# Faced.net
KiCad netlist of a schematic drawn in EAGLE
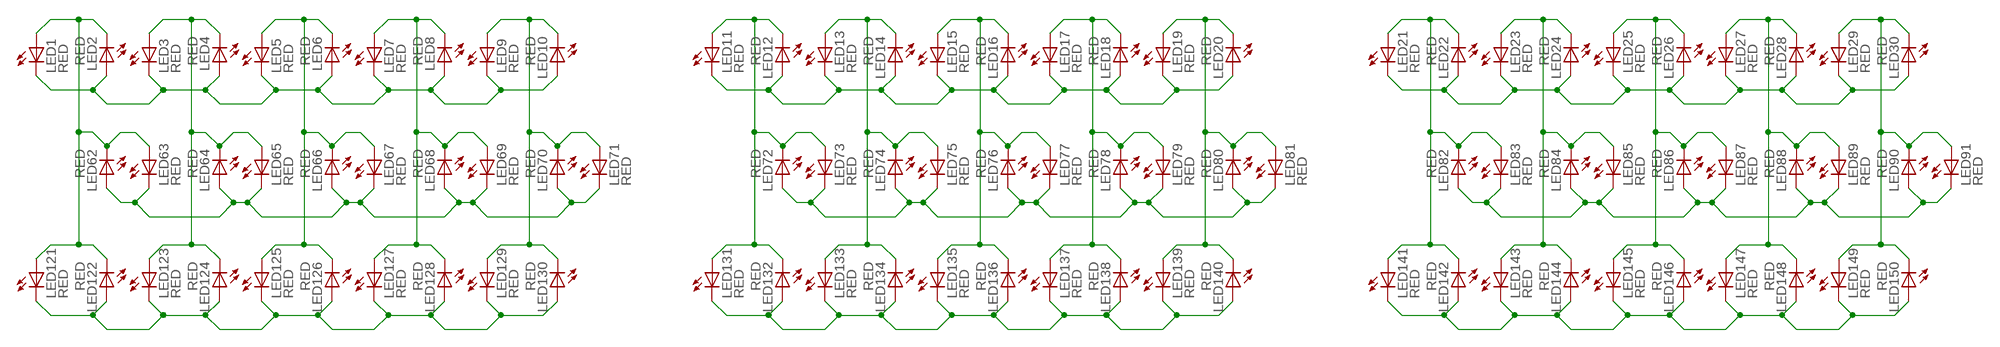
[diagram p0: schematic, sheet 1, part 1 of 2]
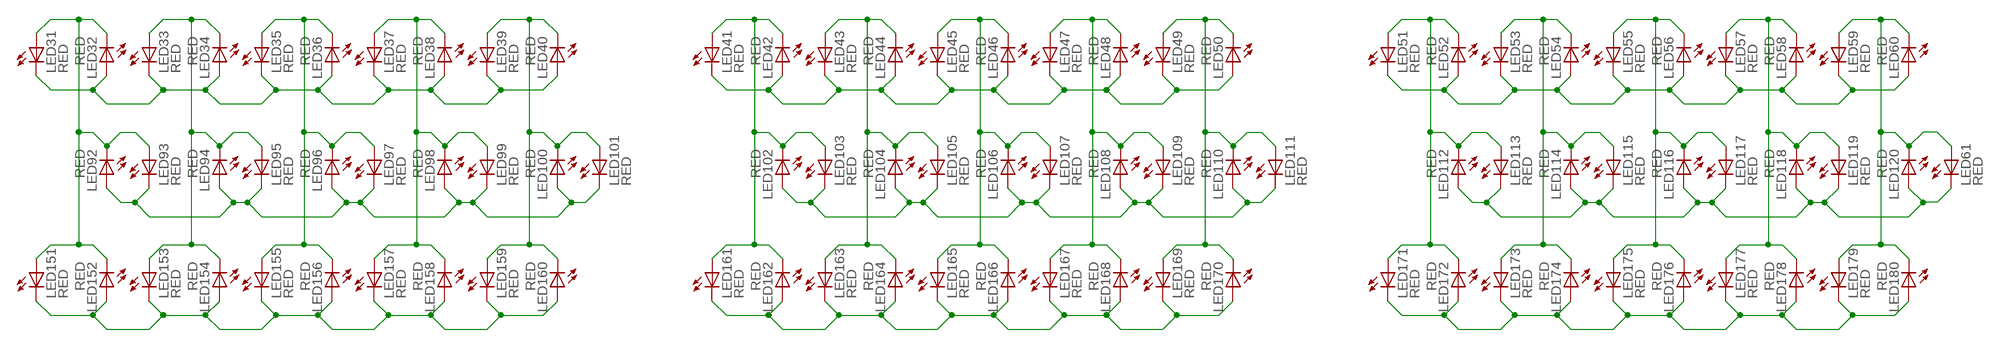
[diagram p1: schematic, sheet 1, part 2 of 2]

(export (version "E")
  (design (tool "Eeschema 10.0.6"))
  (components
    (comp (ref "LED1")
      (value "RED")
      (footprint "eagle-import:LED-0603")
      (libsource (lib "eagle-import") (part "LED0603"))
    )
    (comp (ref "LED2")
      (value "RED")
      (footprint "eagle-import:LED-0603")
      (libsource (lib "eagle-import") (part "LED0603"))
    )
    (comp (ref "LED3")
      (value "RED")
      (footprint "eagle-import:LED-0603")
      (libsource (lib "eagle-import") (part "LED0603"))
    )
    (comp (ref "LED4")
      (value "RED")
      (footprint "eagle-import:LED-0603")
      (libsource (lib "eagle-import") (part "LED0603"))
    )
    (comp (ref "LED5")
      (value "RED")
      (footprint "eagle-import:LED-0603")
      (libsource (lib "eagle-import") (part "LED0603"))
    )
    (comp (ref "LED6")
      (value "RED")
      (footprint "eagle-import:LED-0603")
      (libsource (lib "eagle-import") (part "LED0603"))
    )
    (comp (ref "LED7")
      (value "RED")
      (footprint "eagle-import:LED-0603")
      (libsource (lib "eagle-import") (part "LED0603"))
    )
    (comp (ref "LED8")
      (value "RED")
      (footprint "eagle-import:LED-0603")
      (libsource (lib "eagle-import") (part "LED0603"))
    )
    (comp (ref "LED9")
      (value "RED")
      (footprint "eagle-import:LED-0603")
      (libsource (lib "eagle-import") (part "LED0603"))
    )
    (comp (ref "LED10")
      (value "RED")
      (footprint "eagle-import:LED-0603")
      (libsource (lib "eagle-import") (part "LED0603"))
    )
    (comp (ref "LED11")
      (value "RED")
      (footprint "eagle-import:LED-0603")
      (libsource (lib "eagle-import") (part "LED0603"))
    )
    (comp (ref "LED12")
      (value "RED")
      (footprint "eagle-import:LED-0603")
      (libsource (lib "eagle-import") (part "LED0603"))
    )
    (comp (ref "LED13")
      (value "RED")
      (footprint "eagle-import:LED-0603")
      (libsource (lib "eagle-import") (part "LED0603"))
    )
    (comp (ref "LED14")
      (value "RED")
      (footprint "eagle-import:LED-0603")
      (libsource (lib "eagle-import") (part "LED0603"))
    )
    (comp (ref "LED15")
      (value "RED")
      (footprint "eagle-import:LED-0603")
      (libsource (lib "eagle-import") (part "LED0603"))
    )
    (comp (ref "LED16")
      (value "RED")
      (footprint "eagle-import:LED-0603")
      (libsource (lib "eagle-import") (part "LED0603"))
    )
    (comp (ref "LED17")
      (value "RED")
      (footprint "eagle-import:LED-0603")
      (libsource (lib "eagle-import") (part "LED0603"))
    )
    (comp (ref "LED18")
      (value "RED")
      (footprint "eagle-import:LED-0603")
      (libsource (lib "eagle-import") (part "LED0603"))
    )
    (comp (ref "LED19")
      (value "RED")
      (footprint "eagle-import:LED-0603")
      (libsource (lib "eagle-import") (part "LED0603"))
    )
    (comp (ref "LED20")
      (value "RED")
      (footprint "eagle-import:LED-0603")
      (libsource (lib "eagle-import") (part "LED0603"))
    )
    (comp (ref "LED21")
      (value "RED")
      (footprint "eagle-import:LED-0603")
      (libsource (lib "eagle-import") (part "LED0603"))
    )
    (comp (ref "LED22")
      (value "RED")
      (footprint "eagle-import:LED-0603")
      (libsource (lib "eagle-import") (part "LED0603"))
    )
    (comp (ref "LED23")
      (value "RED")
      (footprint "eagle-import:LED-0603")
      (libsource (lib "eagle-import") (part "LED0603"))
    )
    (comp (ref "LED24")
      (value "RED")
      (footprint "eagle-import:LED-0603")
      (libsource (lib "eagle-import") (part "LED0603"))
    )
    (comp (ref "LED25")
      (value "RED")
      (footprint "eagle-import:LED-0603")
      (libsource (lib "eagle-import") (part "LED0603"))
    )
    (comp (ref "LED26")
      (value "RED")
      (footprint "eagle-import:LED-0603")
      (libsource (lib "eagle-import") (part "LED0603"))
    )
    (comp (ref "LED27")
      (value "RED")
      (footprint "eagle-import:LED-0603")
      (libsource (lib "eagle-import") (part "LED0603"))
    )
    (comp (ref "LED28")
      (value "RED")
      (footprint "eagle-import:LED-0603")
      (libsource (lib "eagle-import") (part "LED0603"))
    )
    (comp (ref "LED29")
      (value "RED")
      (footprint "eagle-import:LED-0603")
      (libsource (lib "eagle-import") (part "LED0603"))
    )
    (comp (ref "LED30")
      (value "RED")
      (footprint "eagle-import:LED-0603")
      (libsource (lib "eagle-import") (part "LED0603"))
    )
    (comp (ref "LED31")
      (value "RED")
      (footprint "eagle-import:LED-0603")
      (libsource (lib "eagle-import") (part "LED0603"))
    )
    (comp (ref "LED32")
      (value "RED")
      (footprint "eagle-import:LED-0603")
      (libsource (lib "eagle-import") (part "LED0603"))
    )
    (comp (ref "LED33")
      (value "RED")
      (footprint "eagle-import:LED-0603")
      (libsource (lib "eagle-import") (part "LED0603"))
    )
    (comp (ref "LED34")
      (value "RED")
      (footprint "eagle-import:LED-0603")
      (libsource (lib "eagle-import") (part "LED0603"))
    )
    (comp (ref "LED35")
      (value "RED")
      (footprint "eagle-import:LED-0603")
      (libsource (lib "eagle-import") (part "LED0603"))
    )
    (comp (ref "LED36")
      (value "RED")
      (footprint "eagle-import:LED-0603")
      (libsource (lib "eagle-import") (part "LED0603"))
    )
    (comp (ref "LED37")
      (value "RED")
      (footprint "eagle-import:LED-0603")
      (libsource (lib "eagle-import") (part "LED0603"))
    )
    (comp (ref "LED38")
      (value "RED")
      (footprint "eagle-import:LED-0603")
      (libsource (lib "eagle-import") (part "LED0603"))
    )
    (comp (ref "LED39")
      (value "RED")
      (footprint "eagle-import:LED-0603")
      (libsource (lib "eagle-import") (part "LED0603"))
    )
    (comp (ref "LED40")
      (value "RED")
      (footprint "eagle-import:LED-0603")
      (libsource (lib "eagle-import") (part "LED0603"))
    )
    (comp (ref "LED41")
      (value "RED")
      (footprint "eagle-import:LED-0603")
      (libsource (lib "eagle-import") (part "LED0603"))
    )
    (comp (ref "LED42")
      (value "RED")
      (footprint "eagle-import:LED-0603")
      (libsource (lib "eagle-import") (part "LED0603"))
    )
    (comp (ref "LED43")
      (value "RED")
      (footprint "eagle-import:LED-0603")
      (libsource (lib "eagle-import") (part "LED0603"))
    )
    (comp (ref "LED44")
      (value "RED")
      (footprint "eagle-import:LED-0603")
      (libsource (lib "eagle-import") (part "LED0603"))
    )
    (comp (ref "LED45")
      (value "RED")
      (footprint "eagle-import:LED-0603")
      (libsource (lib "eagle-import") (part "LED0603"))
    )
    (comp (ref "LED46")
      (value "RED")
      (footprint "eagle-import:LED-0603")
      (libsource (lib "eagle-import") (part "LED0603"))
    )
    (comp (ref "LED47")
      (value "RED")
      (footprint "eagle-import:LED-0603")
      (libsource (lib "eagle-import") (part "LED0603"))
    )
    (comp (ref "LED48")
      (value "RED")
      (footprint "eagle-import:LED-0603")
      (libsource (lib "eagle-import") (part "LED0603"))
    )
    (comp (ref "LED49")
      (value "RED")
      (footprint "eagle-import:LED-0603")
      (libsource (lib "eagle-import") (part "LED0603"))
    )
    (comp (ref "LED50")
      (value "RED")
      (footprint "eagle-import:LED-0603")
      (libsource (lib "eagle-import") (part "LED0603"))
    )
    (comp (ref "LED51")
      (value "RED")
      (footprint "eagle-import:LED-0603")
      (libsource (lib "eagle-import") (part "LED0603"))
    )
    (comp (ref "LED52")
      (value "RED")
      (footprint "eagle-import:LED-0603")
      (libsource (lib "eagle-import") (part "LED0603"))
    )
    (comp (ref "LED53")
      (value "RED")
      (footprint "eagle-import:LED-0603")
      (libsource (lib "eagle-import") (part "LED0603"))
    )
    (comp (ref "LED54")
      (value "RED")
      (footprint "eagle-import:LED-0603")
      (libsource (lib "eagle-import") (part "LED0603"))
    )
    (comp (ref "LED55")
      (value "RED")
      (footprint "eagle-import:LED-0603")
      (libsource (lib "eagle-import") (part "LED0603"))
    )
    (comp (ref "LED56")
      (value "RED")
      (footprint "eagle-import:LED-0603")
      (libsource (lib "eagle-import") (part "LED0603"))
    )
    (comp (ref "LED57")
      (value "RED")
      (footprint "eagle-import:LED-0603")
      (libsource (lib "eagle-import") (part "LED0603"))
    )
    (comp (ref "LED58")
      (value "RED")
      (footprint "eagle-import:LED-0603")
      (libsource (lib "eagle-import") (part "LED0603"))
    )
    (comp (ref "LED59")
      (value "RED")
      (footprint "eagle-import:LED-0603")
      (libsource (lib "eagle-import") (part "LED0603"))
    )
    (comp (ref "LED60")
      (value "RED")
      (footprint "eagle-import:LED-0603")
      (libsource (lib "eagle-import") (part "LED0603"))
    )
    (comp (ref "LED61")
      (value "RED")
      (footprint "eagle-import:LED-0603")
      (libsource (lib "eagle-import") (part "LED0603"))
    )
    (comp (ref "LED62")
      (value "RED")
      (footprint "eagle-import:LED-0603")
      (libsource (lib "eagle-import") (part "LED0603"))
    )
    (comp (ref "LED63")
      (value "RED")
      (footprint "eagle-import:LED-0603")
      (libsource (lib "eagle-import") (part "LED0603"))
    )
    (comp (ref "LED64")
      (value "RED")
      (footprint "eagle-import:LED-0603")
      (libsource (lib "eagle-import") (part "LED0603"))
    )
    (comp (ref "LED65")
      (value "RED")
      (footprint "eagle-import:LED-0603")
      (libsource (lib "eagle-import") (part "LED0603"))
    )
    (comp (ref "LED66")
      (value "RED")
      (footprint "eagle-import:LED-0603")
      (libsource (lib "eagle-import") (part "LED0603"))
    )
    (comp (ref "LED67")
      (value "RED")
      (footprint "eagle-import:LED-0603")
      (libsource (lib "eagle-import") (part "LED0603"))
    )
    (comp (ref "LED68")
      (value "RED")
      (footprint "eagle-import:LED-0603")
      (libsource (lib "eagle-import") (part "LED0603"))
    )
    (comp (ref "LED69")
      (value "RED")
      (footprint "eagle-import:LED-0603")
      (libsource (lib "eagle-import") (part "LED0603"))
    )
    (comp (ref "LED70")
      (value "RED")
      (footprint "eagle-import:LED-0603")
      (libsource (lib "eagle-import") (part "LED0603"))
    )
    (comp (ref "LED71")
      (value "RED")
      (footprint "eagle-import:LED-0603")
      (libsource (lib "eagle-import") (part "LED0603"))
    )
    (comp (ref "LED72")
      (value "RED")
      (footprint "eagle-import:LED-0603")
      (libsource (lib "eagle-import") (part "LED0603"))
    )
    (comp (ref "LED73")
      (value "RED")
      (footprint "eagle-import:LED-0603")
      (libsource (lib "eagle-import") (part "LED0603"))
    )
    (comp (ref "LED74")
      (value "RED")
      (footprint "eagle-import:LED-0603")
      (libsource (lib "eagle-import") (part "LED0603"))
    )
    (comp (ref "LED75")
      (value "RED")
      (footprint "eagle-import:LED-0603")
      (libsource (lib "eagle-import") (part "LED0603"))
    )
    (comp (ref "LED76")
      (value "RED")
      (footprint "eagle-import:LED-0603")
      (libsource (lib "eagle-import") (part "LED0603"))
    )
    (comp (ref "LED77")
      (value "RED")
      (footprint "eagle-import:LED-0603")
      (libsource (lib "eagle-import") (part "LED0603"))
    )
    (comp (ref "LED78")
      (value "RED")
      (footprint "eagle-import:LED-0603")
      (libsource (lib "eagle-import") (part "LED0603"))
    )
    (comp (ref "LED79")
      (value "RED")
      (footprint "eagle-import:LED-0603")
      (libsource (lib "eagle-import") (part "LED0603"))
    )
    (comp (ref "LED80")
      (value "RED")
      (footprint "eagle-import:LED-0603")
      (libsource (lib "eagle-import") (part "LED0603"))
    )
    (comp (ref "LED81")
      (value "RED")
      (footprint "eagle-import:LED-0603")
      (libsource (lib "eagle-import") (part "LED0603"))
    )
    (comp (ref "LED82")
      (value "RED")
      (footprint "eagle-import:LED-0603")
      (libsource (lib "eagle-import") (part "LED0603"))
    )
    (comp (ref "LED83")
      (value "RED")
      (footprint "eagle-import:LED-0603")
      (libsource (lib "eagle-import") (part "LED0603"))
    )
    (comp (ref "LED84")
      (value "RED")
      (footprint "eagle-import:LED-0603")
      (libsource (lib "eagle-import") (part "LED0603"))
    )
    (comp (ref "LED85")
      (value "RED")
      (footprint "eagle-import:LED-0603")
      (libsource (lib "eagle-import") (part "LED0603"))
    )
    (comp (ref "LED86")
      (value "RED")
      (footprint "eagle-import:LED-0603")
      (libsource (lib "eagle-import") (part "LED0603"))
    )
    (comp (ref "LED87")
      (value "RED")
      (footprint "eagle-import:LED-0603")
      (libsource (lib "eagle-import") (part "LED0603"))
    )
    (comp (ref "LED88")
      (value "RED")
      (footprint "eagle-import:LED-0603")
      (libsource (lib "eagle-import") (part "LED0603"))
    )
    (comp (ref "LED89")
      (value "RED")
      (footprint "eagle-import:LED-0603")
      (libsource (lib "eagle-import") (part "LED0603"))
    )
    (comp (ref "LED90")
      (value "RED")
      (footprint "eagle-import:LED-0603")
      (libsource (lib "eagle-import") (part "LED0603"))
    )
    (comp (ref "LED91")
      (value "RED")
      (footprint "eagle-import:LED-0603")
      (libsource (lib "eagle-import") (part "LED0603"))
    )
    (comp (ref "LED92")
      (value "RED")
      (footprint "eagle-import:LED-0603")
      (libsource (lib "eagle-import") (part "LED0603"))
    )
    (comp (ref "LED93")
      (value "RED")
      (footprint "eagle-import:LED-0603")
      (libsource (lib "eagle-import") (part "LED0603"))
    )
    (comp (ref "LED94")
      (value "RED")
      (footprint "eagle-import:LED-0603")
      (libsource (lib "eagle-import") (part "LED0603"))
    )
    (comp (ref "LED95")
      (value "RED")
      (footprint "eagle-import:LED-0603")
      (libsource (lib "eagle-import") (part "LED0603"))
    )
    (comp (ref "LED96")
      (value "RED")
      (footprint "eagle-import:LED-0603")
      (libsource (lib "eagle-import") (part "LED0603"))
    )
    (comp (ref "LED97")
      (value "RED")
      (footprint "eagle-import:LED-0603")
      (libsource (lib "eagle-import") (part "LED0603"))
    )
    (comp (ref "LED98")
      (value "RED")
      (footprint "eagle-import:LED-0603")
      (libsource (lib "eagle-import") (part "LED0603"))
    )
    (comp (ref "LED99")
      (value "RED")
      (footprint "eagle-import:LED-0603")
      (libsource (lib "eagle-import") (part "LED0603"))
    )
    (comp (ref "LED100")
      (value "RED")
      (footprint "eagle-import:LED-0603")
      (libsource (lib "eagle-import") (part "LED0603"))
    )
    (comp (ref "LED101")
      (value "RED")
      (footprint "eagle-import:LED-0603")
      (libsource (lib "eagle-import") (part "LED0603"))
    )
    (comp (ref "LED102")
      (value "RED")
      (footprint "eagle-import:LED-0603")
      (libsource (lib "eagle-import") (part "LED0603"))
    )
    (comp (ref "LED103")
      (value "RED")
      (footprint "eagle-import:LED-0603")
      (libsource (lib "eagle-import") (part "LED0603"))
    )
    (comp (ref "LED104")
      (value "RED")
      (footprint "eagle-import:LED-0603")
      (libsource (lib "eagle-import") (part "LED0603"))
    )
    (comp (ref "LED105")
      (value "RED")
      (footprint "eagle-import:LED-0603")
      (libsource (lib "eagle-import") (part "LED0603"))
    )
    (comp (ref "LED106")
      (value "RED")
      (footprint "eagle-import:LED-0603")
      (libsource (lib "eagle-import") (part "LED0603"))
    )
    (comp (ref "LED107")
      (value "RED")
      (footprint "eagle-import:LED-0603")
      (libsource (lib "eagle-import") (part "LED0603"))
    )
    (comp (ref "LED108")
      (value "RED")
      (footprint "eagle-import:LED-0603")
      (libsource (lib "eagle-import") (part "LED0603"))
    )
    (comp (ref "LED109")
      (value "RED")
      (footprint "eagle-import:LED-0603")
      (libsource (lib "eagle-import") (part "LED0603"))
    )
    (comp (ref "LED110")
      (value "RED")
      (footprint "eagle-import:LED-0603")
      (libsource (lib "eagle-import") (part "LED0603"))
    )
    (comp (ref "LED111")
      (value "RED")
      (footprint "eagle-import:LED-0603")
      (libsource (lib "eagle-import") (part "LED0603"))
    )
    (comp (ref "LED112")
      (value "RED")
      (footprint "eagle-import:LED-0603")
      (libsource (lib "eagle-import") (part "LED0603"))
    )
    (comp (ref "LED113")
      (value "RED")
      (footprint "eagle-import:LED-0603")
      (libsource (lib "eagle-import") (part "LED0603"))
    )
    (comp (ref "LED114")
      (value "RED")
      (footprint "eagle-import:LED-0603")
      (libsource (lib "eagle-import") (part "LED0603"))
    )
    (comp (ref "LED115")
      (value "RED")
      (footprint "eagle-import:LED-0603")
      (libsource (lib "eagle-import") (part "LED0603"))
    )
    (comp (ref "LED116")
      (value "RED")
      (footprint "eagle-import:LED-0603")
      (libsource (lib "eagle-import") (part "LED0603"))
    )
    (comp (ref "LED117")
      (value "RED")
      (footprint "eagle-import:LED-0603")
      (libsource (lib "eagle-import") (part "LED0603"))
    )
    (comp (ref "LED118")
      (value "RED")
      (footprint "eagle-import:LED-0603")
      (libsource (lib "eagle-import") (part "LED0603"))
    )
    (comp (ref "LED119")
      (value "RED")
      (footprint "eagle-import:LED-0603")
      (libsource (lib "eagle-import") (part "LED0603"))
    )
    (comp (ref "LED120")
      (value "RED")
      (footprint "eagle-import:LED-0603")
      (libsource (lib "eagle-import") (part "LED0603"))
    )
    (comp (ref "LED121")
      (value "RED")
      (footprint "eagle-import:LED-0603")
      (libsource (lib "eagle-import") (part "LED0603"))
    )
    (comp (ref "LED122")
      (value "RED")
      (footprint "eagle-import:LED-0603")
      (libsource (lib "eagle-import") (part "LED0603"))
    )
    (comp (ref "LED123")
      (value "RED")
      (footprint "eagle-import:LED-0603")
      (libsource (lib "eagle-import") (part "LED0603"))
    )
    (comp (ref "LED124")
      (value "RED")
      (footprint "eagle-import:LED-0603")
      (libsource (lib "eagle-import") (part "LED0603"))
    )
    (comp (ref "LED125")
      (value "RED")
      (footprint "eagle-import:LED-0603")
      (libsource (lib "eagle-import") (part "LED0603"))
    )
    (comp (ref "LED126")
      (value "RED")
      (footprint "eagle-import:LED-0603")
      (libsource (lib "eagle-import") (part "LED0603"))
    )
    (comp (ref "LED127")
      (value "RED")
      (footprint "eagle-import:LED-0603")
      (libsource (lib "eagle-import") (part "LED0603"))
    )
    (comp (ref "LED128")
      (value "RED")
      (footprint "eagle-import:LED-0603")
      (libsource (lib "eagle-import") (part "LED0603"))
    )
    (comp (ref "LED129")
      (value "RED")
      (footprint "eagle-import:LED-0603")
      (libsource (lib "eagle-import") (part "LED0603"))
    )
    (comp (ref "LED130")
      (value "RED")
      (footprint "eagle-import:LED-0603")
      (libsource (lib "eagle-import") (part "LED0603"))
    )
    (comp (ref "LED131")
      (value "RED")
      (footprint "eagle-import:LED-0603")
      (libsource (lib "eagle-import") (part "LED0603"))
    )
    (comp (ref "LED132")
      (value "RED")
      (footprint "eagle-import:LED-0603")
      (libsource (lib "eagle-import") (part "LED0603"))
    )
    (comp (ref "LED133")
      (value "RED")
      (footprint "eagle-import:LED-0603")
      (libsource (lib "eagle-import") (part "LED0603"))
    )
    (comp (ref "LED134")
      (value "RED")
      (footprint "eagle-import:LED-0603")
      (libsource (lib "eagle-import") (part "LED0603"))
    )
    (comp (ref "LED135")
      (value "RED")
      (footprint "eagle-import:LED-0603")
      (libsource (lib "eagle-import") (part "LED0603"))
    )
    (comp (ref "LED136")
      (value "RED")
      (footprint "eagle-import:LED-0603")
      (libsource (lib "eagle-import") (part "LED0603"))
    )
    (comp (ref "LED137")
      (value "RED")
      (footprint "eagle-import:LED-0603")
      (libsource (lib "eagle-import") (part "LED0603"))
    )
    (comp (ref "LED138")
      (value "RED")
      (footprint "eagle-import:LED-0603")
      (libsource (lib "eagle-import") (part "LED0603"))
    )
    (comp (ref "LED139")
      (value "RED")
      (footprint "eagle-import:LED-0603")
      (libsource (lib "eagle-import") (part "LED0603"))
    )
    (comp (ref "LED140")
      (value "RED")
      (footprint "eagle-import:LED-0603")
      (libsource (lib "eagle-import") (part "LED0603"))
    )
    (comp (ref "LED141")
      (value "RED")
      (footprint "eagle-import:LED-0603")
      (libsource (lib "eagle-import") (part "LED0603"))
    )
    (comp (ref "LED142")
      (value "RED")
      (footprint "eagle-import:LED-0603")
      (libsource (lib "eagle-import") (part "LED0603"))
    )
    (comp (ref "LED143")
      (value "RED")
      (footprint "eagle-import:LED-0603")
      (libsource (lib "eagle-import") (part "LED0603"))
    )
    (comp (ref "LED144")
      (value "RED")
      (footprint "eagle-import:LED-0603")
      (libsource (lib "eagle-import") (part "LED0603"))
    )
    (comp (ref "LED145")
      (value "RED")
      (footprint "eagle-import:LED-0603")
      (libsource (lib "eagle-import") (part "LED0603"))
    )
    (comp (ref "LED146")
      (value "RED")
      (footprint "eagle-import:LED-0603")
      (libsource (lib "eagle-import") (part "LED0603"))
    )
    (comp (ref "LED147")
      (value "RED")
      (footprint "eagle-import:LED-0603")
      (libsource (lib "eagle-import") (part "LED0603"))
    )
    (comp (ref "LED148")
      (value "RED")
      (footprint "eagle-import:LED-0603")
      (libsource (lib "eagle-import") (part "LED0603"))
    )
    (comp (ref "LED149")
      (value "RED")
      (footprint "eagle-import:LED-0603")
      (libsource (lib "eagle-import") (part "LED0603"))
    )
    (comp (ref "LED150")
      (value "RED")
      (footprint "eagle-import:LED-0603")
      (libsource (lib "eagle-import") (part "LED0603"))
    )
    (comp (ref "LED151")
      (value "RED")
      (footprint "eagle-import:LED-0603")
      (libsource (lib "eagle-import") (part "LED0603"))
    )
    (comp (ref "LED152")
      (value "RED")
      (footprint "eagle-import:LED-0603")
      (libsource (lib "eagle-import") (part "LED0603"))
    )
    (comp (ref "LED153")
      (value "RED")
      (footprint "eagle-import:LED-0603")
      (libsource (lib "eagle-import") (part "LED0603"))
    )
    (comp (ref "LED154")
      (value "RED")
      (footprint "eagle-import:LED-0603")
      (libsource (lib "eagle-import") (part "LED0603"))
    )
    (comp (ref "LED155")
      (value "RED")
      (footprint "eagle-import:LED-0603")
      (libsource (lib "eagle-import") (part "LED0603"))
    )
    (comp (ref "LED156")
      (value "RED")
      (footprint "eagle-import:LED-0603")
      (libsource (lib "eagle-import") (part "LED0603"))
    )
    (comp (ref "LED157")
      (value "RED")
      (footprint "eagle-import:LED-0603")
      (libsource (lib "eagle-import") (part "LED0603"))
    )
    (comp (ref "LED158")
      (value "RED")
      (footprint "eagle-import:LED-0603")
      (libsource (lib "eagle-import") (part "LED0603"))
    )
    (comp (ref "LED159")
      (value "RED")
      (footprint "eagle-import:LED-0603")
      (libsource (lib "eagle-import") (part "LED0603"))
    )
    (comp (ref "LED160")
      (value "RED")
      (footprint "eagle-import:LED-0603")
      (libsource (lib "eagle-import") (part "LED0603"))
    )
    (comp (ref "LED161")
      (value "RED")
      (footprint "eagle-import:LED-0603")
      (libsource (lib "eagle-import") (part "LED0603"))
    )
    (comp (ref "LED162")
      (value "RED")
      (footprint "eagle-import:LED-0603")
      (libsource (lib "eagle-import") (part "LED0603"))
    )
    (comp (ref "LED163")
      (value "RED")
      (footprint "eagle-import:LED-0603")
      (libsource (lib "eagle-import") (part "LED0603"))
    )
    (comp (ref "LED164")
      (value "RED")
      (footprint "eagle-import:LED-0603")
      (libsource (lib "eagle-import") (part "LED0603"))
    )
    (comp (ref "LED165")
      (value "RED")
      (footprint "eagle-import:LED-0603")
      (libsource (lib "eagle-import") (part "LED0603"))
    )
    (comp (ref "LED166")
      (value "RED")
      (footprint "eagle-import:LED-0603")
      (libsource (lib "eagle-import") (part "LED0603"))
    )
    (comp (ref "LED167")
      (value "RED")
      (footprint "eagle-import:LED-0603")
      (libsource (lib "eagle-import") (part "LED0603"))
    )
    (comp (ref "LED168")
      (value "RED")
      (footprint "eagle-import:LED-0603")
      (libsource (lib "eagle-import") (part "LED0603"))
    )
    (comp (ref "LED169")
      (value "RED")
      (footprint "eagle-import:LED-0603")
      (libsource (lib "eagle-import") (part "LED0603"))
    )
    (comp (ref "LED170")
      (value "RED")
      (footprint "eagle-import:LED-0603")
      (libsource (lib "eagle-import") (part "LED0603"))
    )
    (comp (ref "LED171")
      (value "RED")
      (footprint "eagle-import:LED-0603")
      (libsource (lib "eagle-import") (part "LED0603"))
    )
    (comp (ref "LED172")
      (value "RED")
      (footprint "eagle-import:LED-0603")
      (libsource (lib "eagle-import") (part "LED0603"))
    )
    (comp (ref "LED173")
      (value "RED")
      (footprint "eagle-import:LED-0603")
      (libsource (lib "eagle-import") (part "LED0603"))
    )
    (comp (ref "LED174")
      (value "RED")
      (footprint "eagle-import:LED-0603")
      (libsource (lib "eagle-import") (part "LED0603"))
    )
    (comp (ref "LED175")
      (value "RED")
      (footprint "eagle-import:LED-0603")
      (libsource (lib "eagle-import") (part "LED0603"))
    )
    (comp (ref "LED176")
      (value "RED")
      (footprint "eagle-import:LED-0603")
      (libsource (lib "eagle-import") (part "LED0603"))
    )
    (comp (ref "LED177")
      (value "RED")
      (footprint "eagle-import:LED-0603")
      (libsource (lib "eagle-import") (part "LED0603"))
    )
    (comp (ref "LED178")
      (value "RED")
      (footprint "eagle-import:LED-0603")
      (libsource (lib "eagle-import") (part "LED0603"))
    )
    (comp (ref "LED179")
      (value "RED")
      (footprint "eagle-import:LED-0603")
      (libsource (lib "eagle-import") (part "LED0603"))
    )
    (comp (ref "LED180")
      (value "RED")
      (footprint "eagle-import:LED-0603")
      (libsource (lib "eagle-import") (part "LED0603"))
    )
  )
  (nets
    (net (code "1") (name "Net-(LED1-PadA)") (class "Default")
      (node (ref "LED1") (pin "A") (pinfunction "A_A") (pintype "passive"))
      (node (ref "LED121") (pin "A") (pinfunction "A_A") (pintype "passive"))
      (node (ref "LED122") (pin "C") (pinfunction "C_C") (pintype "passive"))
      (node (ref "LED2") (pin "C") (pinfunction "C_C") (pintype "passive"))
      (node (ref "LED62") (pin "C") (pinfunction "C_C") (pintype "passive"))
      (node (ref "LED63") (pin "A") (pinfunction "A_A") (pintype "passive"))
    )
    (net (code "2") (name "Net-(LED1-PadC)") (class "Default")
      (node (ref "LED1") (pin "C") (pinfunction "C_C") (pintype "passive"))
      (node (ref "LED10") (pin "A") (pinfunction "A_A") (pintype "passive"))
      (node (ref "LED2") (pin "A") (pinfunction "A_A") (pintype "passive"))
      (node (ref "LED3") (pin "C") (pinfunction "C_C") (pintype "passive"))
      (node (ref "LED4") (pin "A") (pinfunction "A_A") (pintype "passive"))
      (node (ref "LED5") (pin "C") (pinfunction "C_C") (pintype "passive"))
      (node (ref "LED6") (pin "A") (pinfunction "A_A") (pintype "passive"))
      (node (ref "LED7") (pin "C") (pinfunction "C_C") (pintype "passive"))
      (node (ref "LED8") (pin "A") (pinfunction "A_A") (pintype "passive"))
      (node (ref "LED9") (pin "C") (pinfunction "C_C") (pintype "passive"))
    )
    (net (code "3") (name "Net-(LED10-PadC)") (class "Default")
      (node (ref "LED10") (pin "C") (pinfunction "C_C") (pintype "passive"))
      (node (ref "LED129") (pin "A") (pinfunction "A_A") (pintype "passive"))
      (node (ref "LED130") (pin "C") (pinfunction "C_C") (pintype "passive"))
      (node (ref "LED70") (pin "C") (pinfunction "C_C") (pintype "passive"))
      (node (ref "LED71") (pin "A") (pinfunction "A_A") (pintype "passive"))
      (node (ref "LED9") (pin "A") (pinfunction "A_A") (pintype "passive"))
    )
    (net (code "4") (name "Net-(LED11-PadA)") (class "Default")
      (node (ref "LED11") (pin "A") (pinfunction "A_A") (pintype "passive"))
      (node (ref "LED12") (pin "C") (pinfunction "C_C") (pintype "passive"))
      (node (ref "LED131") (pin "A") (pinfunction "A_A") (pintype "passive"))
      (node (ref "LED132") (pin "C") (pinfunction "C_C") (pintype "passive"))
      (node (ref "LED72") (pin "C") (pinfunction "C_C") (pintype "passive"))
      (node (ref "LED73") (pin "A") (pinfunction "A_A") (pintype "passive"))
    )
    (net (code "5") (name "Net-(LED11-PadC)") (class "Default")
      (node (ref "LED11") (pin "C") (pinfunction "C_C") (pintype "passive"))
      (node (ref "LED12") (pin "A") (pinfunction "A_A") (pintype "passive"))
      (node (ref "LED13") (pin "C") (pinfunction "C_C") (pintype "passive"))
      (node (ref "LED14") (pin "A") (pinfunction "A_A") (pintype "passive"))
      (node (ref "LED15") (pin "C") (pinfunction "C_C") (pintype "passive"))
      (node (ref "LED16") (pin "A") (pinfunction "A_A") (pintype "passive"))
      (node (ref "LED17") (pin "C") (pinfunction "C_C") (pintype "passive"))
      (node (ref "LED18") (pin "A") (pinfunction "A_A") (pintype "passive"))
      (node (ref "LED19") (pin "C") (pinfunction "C_C") (pintype "passive"))
      (node (ref "LED20") (pin "A") (pinfunction "A_A") (pintype "passive"))
    )
    (net (code "6") (name "Net-(LED13-PadA)") (class "Default")
      (node (ref "LED13") (pin "A") (pinfunction "A_A") (pintype "passive"))
      (node (ref "LED133") (pin "A") (pinfunction "A_A") (pintype "passive"))
      (node (ref "LED134") (pin "C") (pinfunction "C_C") (pintype "passive"))
      (node (ref "LED14") (pin "C") (pinfunction "C_C") (pintype "passive"))
      (node (ref "LED74") (pin "C") (pinfunction "C_C") (pintype "passive"))
      (node (ref "LED75") (pin "A") (pinfunction "A_A") (pintype "passive"))
    )
    (net (code "7") (name "Net-(LED21-PadC)") (class "Default")
      (node (ref "LED21") (pin "C") (pinfunction "C_C") (pintype "passive"))
      (node (ref "LED22") (pin "A") (pinfunction "A_A") (pintype "passive"))
      (node (ref "LED23") (pin "C") (pinfunction "C_C") (pintype "passive"))
      (node (ref "LED24") (pin "A") (pinfunction "A_A") (pintype "passive"))
      (node (ref "LED25") (pin "C") (pinfunction "C_C") (pintype "passive"))
      (node (ref "LED26") (pin "A") (pinfunction "A_A") (pintype "passive"))
      (node (ref "LED27") (pin "C") (pinfunction "C_C") (pintype "passive"))
      (node (ref "LED28") (pin "A") (pinfunction "A_A") (pintype "passive"))
      (node (ref "LED29") (pin "C") (pinfunction "C_C") (pintype "passive"))
      (node (ref "LED30") (pin "A") (pinfunction "A_A") (pintype "passive"))
    )
    (net (code "8") (name "Net-(LED31-PadC)") (class "Default")
      (node (ref "LED31") (pin "C") (pinfunction "C_C") (pintype "passive"))
      (node (ref "LED32") (pin "A") (pinfunction "A_A") (pintype "passive"))
      (node (ref "LED33") (pin "C") (pinfunction "C_C") (pintype "passive"))
      (node (ref "LED34") (pin "A") (pinfunction "A_A") (pintype "passive"))
      (node (ref "LED35") (pin "C") (pinfunction "C_C") (pintype "passive"))
      (node (ref "LED36") (pin "A") (pinfunction "A_A") (pintype "passive"))
      (node (ref "LED37") (pin "C") (pinfunction "C_C") (pintype "passive"))
      (node (ref "LED38") (pin "A") (pinfunction "A_A") (pintype "passive"))
      (node (ref "LED39") (pin "C") (pinfunction "C_C") (pintype "passive"))
      (node (ref "LED40") (pin "A") (pinfunction "A_A") (pintype "passive"))
    )
    (net (code "9") (name "Net-(LED41-PadC)") (class "Default")
      (node (ref "LED41") (pin "C") (pinfunction "C_C") (pintype "passive"))
      (node (ref "LED42") (pin "A") (pinfunction "A_A") (pintype "passive"))
      (node (ref "LED43") (pin "C") (pinfunction "C_C") (pintype "passive"))
      (node (ref "LED44") (pin "A") (pinfunction "A_A") (pintype "passive"))
      (node (ref "LED45") (pin "C") (pinfunction "C_C") (pintype "passive"))
      (node (ref "LED46") (pin "A") (pinfunction "A_A") (pintype "passive"))
      (node (ref "LED47") (pin "C") (pinfunction "C_C") (pintype "passive"))
      (node (ref "LED48") (pin "A") (pinfunction "A_A") (pintype "passive"))
      (node (ref "LED49") (pin "C") (pinfunction "C_C") (pintype "passive"))
      (node (ref "LED50") (pin "A") (pinfunction "A_A") (pintype "passive"))
    )
    (net (code "10") (name "Net-(LED51-PadC)") (class "Default")
      (node (ref "LED51") (pin "C") (pinfunction "C_C") (pintype "passive"))
      (node (ref "LED52") (pin "A") (pinfunction "A_A") (pintype "passive"))
      (node (ref "LED53") (pin "C") (pinfunction "C_C") (pintype "passive"))
      (node (ref "LED54") (pin "A") (pinfunction "A_A") (pintype "passive"))
      (node (ref "LED55") (pin "C") (pinfunction "C_C") (pintype "passive"))
      (node (ref "LED56") (pin "A") (pinfunction "A_A") (pintype "passive"))
      (node (ref "LED57") (pin "C") (pinfunction "C_C") (pintype "passive"))
      (node (ref "LED58") (pin "A") (pinfunction "A_A") (pintype "passive"))
      (node (ref "LED59") (pin "C") (pinfunction "C_C") (pintype "passive"))
      (node (ref "LED60") (pin "A") (pinfunction "A_A") (pintype "passive"))
    )
    (net (code "11") (name "Net-(LED62-PadA)") (class "Default")
      (node (ref "LED62") (pin "A") (pinfunction "A_A") (pintype "passive"))
      (node (ref "LED63") (pin "C") (pinfunction "C_C") (pintype "passive"))
      (node (ref "LED64") (pin "A") (pinfunction "A_A") (pintype "passive"))
      (node (ref "LED65") (pin "C") (pinfunction "C_C") (pintype "passive"))
      (node (ref "LED66") (pin "A") (pinfunction "A_A") (pintype "passive"))
      (node (ref "LED67") (pin "C") (pinfunction "C_C") (pintype "passive"))
      (node (ref "LED68") (pin "A") (pinfunction "A_A") (pintype "passive"))
      (node (ref "LED69") (pin "C") (pinfunction "C_C") (pintype "passive"))
      (node (ref "LED70") (pin "A") (pinfunction "A_A") (pintype "passive"))
      (node (ref "LED71") (pin "C") (pinfunction "C_C") (pintype "passive"))
    )
    (net (code "12") (name "Net-(LED72-PadA)") (class "Default")
      (node (ref "LED72") (pin "A") (pinfunction "A_A") (pintype "passive"))
      (node (ref "LED73") (pin "C") (pinfunction "C_C") (pintype "passive"))
      (node (ref "LED74") (pin "A") (pinfunction "A_A") (pintype "passive"))
      (node (ref "LED75") (pin "C") (pinfunction "C_C") (pintype "passive"))
      (node (ref "LED76") (pin "A") (pinfunction "A_A") (pintype "passive"))
      (node (ref "LED77") (pin "C") (pinfunction "C_C") (pintype "passive"))
      (node (ref "LED78") (pin "A") (pinfunction "A_A") (pintype "passive"))
      (node (ref "LED79") (pin "C") (pinfunction "C_C") (pintype "passive"))
      (node (ref "LED80") (pin "A") (pinfunction "A_A") (pintype "passive"))
      (node (ref "LED81") (pin "C") (pinfunction "C_C") (pintype "passive"))
    )
    (net (code "13") (name "Net-(LED82-PadA)") (class "Default")
      (node (ref "LED82") (pin "A") (pinfunction "A_A") (pintype "passive"))
      (node (ref "LED83") (pin "C") (pinfunction "C_C") (pintype "passive"))
      (node (ref "LED84") (pin "A") (pinfunction "A_A") (pintype "passive"))
      (node (ref "LED85") (pin "C") (pinfunction "C_C") (pintype "passive"))
      (node (ref "LED86") (pin "A") (pinfunction "A_A") (pintype "passive"))
      (node (ref "LED87") (pin "C") (pinfunction "C_C") (pintype "passive"))
      (node (ref "LED88") (pin "A") (pinfunction "A_A") (pintype "passive"))
      (node (ref "LED89") (pin "C") (pinfunction "C_C") (pintype "passive"))
      (node (ref "LED90") (pin "A") (pinfunction "A_A") (pintype "passive"))
      (node (ref "LED91") (pin "C") (pinfunction "C_C") (pintype "passive"))
    )
    (net (code "14") (name "Net-(LED100-PadA)") (class "Default")
      (node (ref "LED100") (pin "A") (pinfunction "A_A") (pintype "passive"))
      (node (ref "LED101") (pin "C") (pinfunction "C_C") (pintype "passive"))
      (node (ref "LED92") (pin "A") (pinfunction "A_A") (pintype "passive"))
      (node (ref "LED93") (pin "C") (pinfunction "C_C") (pintype "passive"))
      (node (ref "LED94") (pin "A") (pinfunction "A_A") (pintype "passive"))
      (node (ref "LED95") (pin "C") (pinfunction "C_C") (pintype "passive"))
      (node (ref "LED96") (pin "A") (pinfunction "A_A") (pintype "passive"))
      (node (ref "LED97") (pin "C") (pinfunction "C_C") (pintype "passive"))
      (node (ref "LED98") (pin "A") (pinfunction "A_A") (pintype "passive"))
      (node (ref "LED99") (pin "C") (pinfunction "C_C") (pintype "passive"))
    )
    (net (code "15") (name "Net-(LED100-PadC)") (class "Default")
      (node (ref "LED100") (pin "C") (pinfunction "C_C") (pintype "passive"))
      (node (ref "LED101") (pin "A") (pinfunction "A_A") (pintype "passive"))
      (node (ref "LED159") (pin "A") (pinfunction "A_A") (pintype "passive"))
      (node (ref "LED160") (pin "C") (pinfunction "C_C") (pintype "passive"))
      (node (ref "LED39") (pin "A") (pinfunction "A_A") (pintype "passive"))
      (node (ref "LED40") (pin "C") (pinfunction "C_C") (pintype "passive"))
    )
    (net (code "16") (name "Net-(LED102-PadA)") (class "Default")
      (node (ref "LED102") (pin "A") (pinfunction "A_A") (pintype "passive"))
      (node (ref "LED103") (pin "C") (pinfunction "C_C") (pintype "passive"))
      (node (ref "LED104") (pin "A") (pinfunction "A_A") (pintype "passive"))
      (node (ref "LED105") (pin "C") (pinfunction "C_C") (pintype "passive"))
      (node (ref "LED106") (pin "A") (pinfunction "A_A") (pintype "passive"))
      (node (ref "LED107") (pin "C") (pinfunction "C_C") (pintype "passive"))
      (node (ref "LED108") (pin "A") (pinfunction "A_A") (pintype "passive"))
      (node (ref "LED109") (pin "C") (pinfunction "C_C") (pintype "passive"))
      (node (ref "LED110") (pin "A") (pinfunction "A_A") (pintype "passive"))
      (node (ref "LED111") (pin "C") (pinfunction "C_C") (pintype "passive"))
    )
    (net (code "17") (name "Net-(LED102-PadC)") (class "Default")
      (node (ref "LED102") (pin "C") (pinfunction "C_C") (pintype "passive"))
      (node (ref "LED103") (pin "A") (pinfunction "A_A") (pintype "passive"))
      (node (ref "LED161") (pin "A") (pinfunction "A_A") (pintype "passive"))
      (node (ref "LED162") (pin "C") (pinfunction "C_C") (pintype "passive"))
      (node (ref "LED41") (pin "A") (pinfunction "A_A") (pintype "passive"))
      (node (ref "LED42") (pin "C") (pinfunction "C_C") (pintype "passive"))
    )
    (net (code "18") (name "Net-(LED104-PadC)") (class "Default")
      (node (ref "LED104") (pin "C") (pinfunction "C_C") (pintype "passive"))
      (node (ref "LED105") (pin "A") (pinfunction "A_A") (pintype "passive"))
      (node (ref "LED163") (pin "A") (pinfunction "A_A") (pintype "passive"))
      (node (ref "LED164") (pin "C") (pinfunction "C_C") (pintype "passive"))
      (node (ref "LED43") (pin "A") (pinfunction "A_A") (pintype "passive"))
      (node (ref "LED44") (pin "C") (pinfunction "C_C") (pintype "passive"))
    )
    (net (code "19") (name "Net-(LED106-PadC)") (class "Default")
      (node (ref "LED106") (pin "C") (pinfunction "C_C") (pintype "passive"))
      (node (ref "LED107") (pin "A") (pinfunction "A_A") (pintype "passive"))
      (node (ref "LED165") (pin "A") (pinfunction "A_A") (pintype "passive"))
      (node (ref "LED166") (pin "C") (pinfunction "C_C") (pintype "passive"))
      (node (ref "LED45") (pin "A") (pinfunction "A_A") (pintype "passive"))
      (node (ref "LED46") (pin "C") (pinfunction "C_C") (pintype "passive"))
    )
    (net (code "20") (name "Net-(LED108-PadC)") (class "Default")
      (node (ref "LED108") (pin "C") (pinfunction "C_C") (pintype "passive"))
      (node (ref "LED109") (pin "A") (pinfunction "A_A") (pintype "passive"))
      (node (ref "LED167") (pin "A") (pinfunction "A_A") (pintype "passive"))
      (node (ref "LED168") (pin "C") (pinfunction "C_C") (pintype "passive"))
      (node (ref "LED47") (pin "A") (pinfunction "A_A") (pintype "passive"))
      (node (ref "LED48") (pin "C") (pinfunction "C_C") (pintype "passive"))
    )
    (net (code "21") (name "Net-(LED110-PadC)") (class "Default")
      (node (ref "LED110") (pin "C") (pinfunction "C_C") (pintype "passive"))
      (node (ref "LED111") (pin "A") (pinfunction "A_A") (pintype "passive"))
      (node (ref "LED169") (pin "A") (pinfunction "A_A") (pintype "passive"))
      (node (ref "LED170") (pin "C") (pinfunction "C_C") (pintype "passive"))
      (node (ref "LED49") (pin "A") (pinfunction "A_A") (pintype "passive"))
      (node (ref "LED50") (pin "C") (pinfunction "C_C") (pintype "passive"))
    )
    (net (code "22") (name "Net-(LED112-PadA)") (class "Default")
      (node (ref "LED112") (pin "A") (pinfunction "A_A") (pintype "passive"))
      (node (ref "LED113") (pin "C") (pinfunction "C_C") (pintype "passive"))
      (node (ref "LED114") (pin "A") (pinfunction "A_A") (pintype "passive"))
      (node (ref "LED115") (pin "C") (pinfunction "C_C") (pintype "passive"))
      (node (ref "LED116") (pin "A") (pinfunction "A_A") (pintype "passive"))
      (node (ref "LED117") (pin "C") (pinfunction "C_C") (pintype "passive"))
      (node (ref "LED118") (pin "A") (pinfunction "A_A") (pintype "passive"))
      (node (ref "LED119") (pin "C") (pinfunction "C_C") (pintype "passive"))
      (node (ref "LED120") (pin "A") (pinfunction "A_A") (pintype "passive"))
      (node (ref "LED61") (pin "C") (pinfunction "C_C") (pintype "passive"))
    )
    (net (code "23") (name "Net-(LED112-PadC)") (class "Default")
      (node (ref "LED112") (pin "C") (pinfunction "C_C") (pintype "passive"))
      (node (ref "LED113") (pin "A") (pinfunction "A_A") (pintype "passive"))
      (node (ref "LED171") (pin "A") (pinfunction "A_A") (pintype "passive"))
      (node (ref "LED172") (pin "C") (pinfunction "C_C") (pintype "passive"))
      (node (ref "LED51") (pin "A") (pinfunction "A_A") (pintype "passive"))
      (node (ref "LED52") (pin "C") (pinfunction "C_C") (pintype "passive"))
    )
    (net (code "24") (name "Net-(LED114-PadC)") (class "Default")
      (node (ref "LED114") (pin "C") (pinfunction "C_C") (pintype "passive"))
      (node (ref "LED115") (pin "A") (pinfunction "A_A") (pintype "passive"))
      (node (ref "LED173") (pin "A") (pinfunction "A_A") (pintype "passive"))
      (node (ref "LED174") (pin "C") (pinfunction "C_C") (pintype "passive"))
      (node (ref "LED53") (pin "A") (pinfunction "A_A") (pintype "passive"))
      (node (ref "LED54") (pin "C") (pinfunction "C_C") (pintype "passive"))
    )
    (net (code "25") (name "Net-(LED116-PadC)") (class "Default")
      (node (ref "LED116") (pin "C") (pinfunction "C_C") (pintype "passive"))
      (node (ref "LED117") (pin "A") (pinfunction "A_A") (pintype "passive"))
      (node (ref "LED175") (pin "A") (pinfunction "A_A") (pintype "passive"))
      (node (ref "LED176") (pin "C") (pinfunction "C_C") (pintype "passive"))
      (node (ref "LED55") (pin "A") (pinfunction "A_A") (pintype "passive"))
      (node (ref "LED56") (pin "C") (pinfunction "C_C") (pintype "passive"))
    )
    (net (code "26") (name "Net-(LED118-PadC)") (class "Default")
      (node (ref "LED118") (pin "C") (pinfunction "C_C") (pintype "passive"))
      (node (ref "LED119") (pin "A") (pinfunction "A_A") (pintype "passive"))
      (node (ref "LED177") (pin "A") (pinfunction "A_A") (pintype "passive"))
      (node (ref "LED178") (pin "C") (pinfunction "C_C") (pintype "passive"))
      (node (ref "LED57") (pin "A") (pinfunction "A_A") (pintype "passive"))
      (node (ref "LED58") (pin "C") (pinfunction "C_C") (pintype "passive"))
    )
    (net (code "27") (name "Net-(LED120-PadC)") (class "Default")
      (node (ref "LED120") (pin "C") (pinfunction "C_C") (pintype "passive"))
      (node (ref "LED179") (pin "A") (pinfunction "A_A") (pintype "passive"))
      (node (ref "LED180") (pin "C") (pinfunction "C_C") (pintype "passive"))
      (node (ref "LED59") (pin "A") (pinfunction "A_A") (pintype "passive"))
      (node (ref "LED60") (pin "C") (pinfunction "C_C") (pintype "passive"))
      (node (ref "LED61") (pin "A") (pinfunction "A_A") (pintype "passive"))
    )
    (net (code "28") (name "Net-(LED121-PadC)") (class "Default")
      (node (ref "LED121") (pin "C") (pinfunction "C_C") (pintype "passive"))
      (node (ref "LED122") (pin "A") (pinfunction "A_A") (pintype "passive"))
      (node (ref "LED123") (pin "C") (pinfunction "C_C") (pintype "passive"))
      (node (ref "LED124") (pin "A") (pinfunction "A_A") (pintype "passive"))
      (node (ref "LED125") (pin "C") (pinfunction "C_C") (pintype "passive"))
      (node (ref "LED126") (pin "A") (pinfunction "A_A") (pintype "passive"))
      (node (ref "LED127") (pin "C") (pinfunction "C_C") (pintype "passive"))
      (node (ref "LED128") (pin "A") (pinfunction "A_A") (pintype "passive"))
      (node (ref "LED129") (pin "C") (pinfunction "C_C") (pintype "passive"))
      (node (ref "LED130") (pin "A") (pinfunction "A_A") (pintype "passive"))
    )
    (net (code "29") (name "Net-(LED123-PadA)") (class "Default")
      (node (ref "LED123") (pin "A") (pinfunction "A_A") (pintype "passive"))
      (node (ref "LED124") (pin "C") (pinfunction "C_C") (pintype "passive"))
      (node (ref "LED3") (pin "A") (pinfunction "A_A") (pintype "passive"))
      (node (ref "LED4") (pin "C") (pinfunction "C_C") (pintype "passive"))
      (node (ref "LED64") (pin "C") (pinfunction "C_C") (pintype "passive"))
      (node (ref "LED65") (pin "A") (pinfunction "A_A") (pintype "passive"))
    )
    (net (code "30") (name "Net-(LED125-PadA)") (class "Default")
      (node (ref "LED125") (pin "A") (pinfunction "A_A") (pintype "passive"))
      (node (ref "LED126") (pin "C") (pinfunction "C_C") (pintype "passive"))
      (node (ref "LED5") (pin "A") (pinfunction "A_A") (pintype "passive"))
      (node (ref "LED6") (pin "C") (pinfunction "C_C") (pintype "passive"))
      (node (ref "LED66") (pin "C") (pinfunction "C_C") (pintype "passive"))
      (node (ref "LED67") (pin "A") (pinfunction "A_A") (pintype "passive"))
    )
    (net (code "31") (name "Net-(LED127-PadA)") (class "Default")
      (node (ref "LED127") (pin "A") (pinfunction "A_A") (pintype "passive"))
      (node (ref "LED128") (pin "C") (pinfunction "C_C") (pintype "passive"))
      (node (ref "LED68") (pin "C") (pinfunction "C_C") (pintype "passive"))
      (node (ref "LED69") (pin "A") (pinfunction "A_A") (pintype "passive"))
      (node (ref "LED7") (pin "A") (pinfunction "A_A") (pintype "passive"))
      (node (ref "LED8") (pin "C") (pinfunction "C_C") (pintype "passive"))
    )
    (net (code "32") (name "Net-(LED131-PadC)") (class "Default")
      (node (ref "LED131") (pin "C") (pinfunction "C_C") (pintype "passive"))
      (node (ref "LED132") (pin "A") (pinfunction "A_A") (pintype "passive"))
      (node (ref "LED133") (pin "C") (pinfunction "C_C") (pintype "passive"))
      (node (ref "LED134") (pin "A") (pinfunction "A_A") (pintype "passive"))
      (node (ref "LED135") (pin "C") (pinfunction "C_C") (pintype "passive"))
      (node (ref "LED136") (pin "A") (pinfunction "A_A") (pintype "passive"))
      (node (ref "LED137") (pin "C") (pinfunction "C_C") (pintype "passive"))
      (node (ref "LED138") (pin "A") (pinfunction "A_A") (pintype "passive"))
      (node (ref "LED139") (pin "C") (pinfunction "C_C") (pintype "passive"))
      (node (ref "LED140") (pin "A") (pinfunction "A_A") (pintype "passive"))
    )
    (net (code "33") (name "Net-(LED135-PadA)") (class "Default")
      (node (ref "LED135") (pin "A") (pinfunction "A_A") (pintype "passive"))
      (node (ref "LED136") (pin "C") (pinfunction "C_C") (pintype "passive"))
      (node (ref "LED15") (pin "A") (pinfunction "A_A") (pintype "passive"))
      (node (ref "LED16") (pin "C") (pinfunction "C_C") (pintype "passive"))
      (node (ref "LED76") (pin "C") (pinfunction "C_C") (pintype "passive"))
      (node (ref "LED77") (pin "A") (pinfunction "A_A") (pintype "passive"))
    )
    (net (code "34") (name "Net-(LED137-PadA)") (class "Default")
      (node (ref "LED137") (pin "A") (pinfunction "A_A") (pintype "passive"))
      (node (ref "LED138") (pin "C") (pinfunction "C_C") (pintype "passive"))
      (node (ref "LED17") (pin "A") (pinfunction "A_A") (pintype "passive"))
      (node (ref "LED18") (pin "C") (pinfunction "C_C") (pintype "passive"))
      (node (ref "LED78") (pin "C") (pinfunction "C_C") (pintype "passive"))
      (node (ref "LED79") (pin "A") (pinfunction "A_A") (pintype "passive"))
    )
    (net (code "35") (name "Net-(LED139-PadA)") (class "Default")
      (node (ref "LED139") (pin "A") (pinfunction "A_A") (pintype "passive"))
      (node (ref "LED140") (pin "C") (pinfunction "C_C") (pintype "passive"))
      (node (ref "LED19") (pin "A") (pinfunction "A_A") (pintype "passive"))
      (node (ref "LED20") (pin "C") (pinfunction "C_C") (pintype "passive"))
      (node (ref "LED80") (pin "C") (pinfunction "C_C") (pintype "passive"))
      (node (ref "LED81") (pin "A") (pinfunction "A_A") (pintype "passive"))
    )
    (net (code "36") (name "Net-(LED141-PadA)") (class "Default")
      (node (ref "LED141") (pin "A") (pinfunction "A_A") (pintype "passive"))
      (node (ref "LED142") (pin "C") (pinfunction "C_C") (pintype "passive"))
      (node (ref "LED21") (pin "A") (pinfunction "A_A") (pintype "passive"))
      (node (ref "LED22") (pin "C") (pinfunction "C_C") (pintype "passive"))
      (node (ref "LED82") (pin "C") (pinfunction "C_C") (pintype "passive"))
      (node (ref "LED83") (pin "A") (pinfunction "A_A") (pintype "passive"))
    )
    (net (code "37") (name "Net-(LED141-PadC)") (class "Default")
      (node (ref "LED141") (pin "C") (pinfunction "C_C") (pintype "passive"))
      (node (ref "LED142") (pin "A") (pinfunction "A_A") (pintype "passive"))
      (node (ref "LED143") (pin "C") (pinfunction "C_C") (pintype "passive"))
      (node (ref "LED144") (pin "A") (pinfunction "A_A") (pintype "passive"))
      (node (ref "LED145") (pin "C") (pinfunction "C_C") (pintype "passive"))
      (node (ref "LED146") (pin "A") (pinfunction "A_A") (pintype "passive"))
      (node (ref "LED147") (pin "C") (pinfunction "C_C") (pintype "passive"))
      (node (ref "LED148") (pin "A") (pinfunction "A_A") (pintype "passive"))
      (node (ref "LED149") (pin "C") (pinfunction "C_C") (pintype "passive"))
      (node (ref "LED150") (pin "A") (pinfunction "A_A") (pintype "passive"))
    )
    (net (code "38") (name "Net-(LED143-PadA)") (class "Default")
      (node (ref "LED143") (pin "A") (pinfunction "A_A") (pintype "passive"))
      (node (ref "LED144") (pin "C") (pinfunction "C_C") (pintype "passive"))
      (node (ref "LED23") (pin "A") (pinfunction "A_A") (pintype "passive"))
      (node (ref "LED24") (pin "C") (pinfunction "C_C") (pintype "passive"))
      (node (ref "LED84") (pin "C") (pinfunction "C_C") (pintype "passive"))
      (node (ref "LED85") (pin "A") (pinfunction "A_A") (pintype "passive"))
    )
    (net (code "39") (name "Net-(LED145-PadA)") (class "Default")
      (node (ref "LED145") (pin "A") (pinfunction "A_A") (pintype "passive"))
      (node (ref "LED146") (pin "C") (pinfunction "C_C") (pintype "passive"))
      (node (ref "LED25") (pin "A") (pinfunction "A_A") (pintype "passive"))
      (node (ref "LED26") (pin "C") (pinfunction "C_C") (pintype "passive"))
      (node (ref "LED86") (pin "C") (pinfunction "C_C") (pintype "passive"))
      (node (ref "LED87") (pin "A") (pinfunction "A_A") (pintype "passive"))
    )
    (net (code "40") (name "Net-(LED147-PadA)") (class "Default")
      (node (ref "LED147") (pin "A") (pinfunction "A_A") (pintype "passive"))
      (node (ref "LED148") (pin "C") (pinfunction "C_C") (pintype "passive"))
      (node (ref "LED27") (pin "A") (pinfunction "A_A") (pintype "passive"))
      (node (ref "LED28") (pin "C") (pinfunction "C_C") (pintype "passive"))
      (node (ref "LED88") (pin "C") (pinfunction "C_C") (pintype "passive"))
      (node (ref "LED89") (pin "A") (pinfunction "A_A") (pintype "passive"))
    )
    (net (code "41") (name "Net-(LED149-PadA)") (class "Default")
      (node (ref "LED149") (pin "A") (pinfunction "A_A") (pintype "passive"))
      (node (ref "LED150") (pin "C") (pinfunction "C_C") (pintype "passive"))
      (node (ref "LED29") (pin "A") (pinfunction "A_A") (pintype "passive"))
      (node (ref "LED30") (pin "C") (pinfunction "C_C") (pintype "passive"))
      (node (ref "LED90") (pin "C") (pinfunction "C_C") (pintype "passive"))
      (node (ref "LED91") (pin "A") (pinfunction "A_A") (pintype "passive"))
    )
    (net (code "42") (name "Net-(LED151-PadA)") (class "Default")
      (node (ref "LED151") (pin "A") (pinfunction "A_A") (pintype "passive"))
      (node (ref "LED152") (pin "C") (pinfunction "C_C") (pintype "passive"))
      (node (ref "LED31") (pin "A") (pinfunction "A_A") (pintype "passive"))
      (node (ref "LED32") (pin "C") (pinfunction "C_C") (pintype "passive"))
      (node (ref "LED92") (pin "C") (pinfunction "C_C") (pintype "passive"))
      (node (ref "LED93") (pin "A") (pinfunction "A_A") (pintype "passive"))
    )
    (net (code "43") (name "Net-(LED151-PadC)") (class "Default")
      (node (ref "LED151") (pin "C") (pinfunction "C_C") (pintype "passive"))
      (node (ref "LED152") (pin "A") (pinfunction "A_A") (pintype "passive"))
      (node (ref "LED153") (pin "C") (pinfunction "C_C") (pintype "passive"))
      (node (ref "LED154") (pin "A") (pinfunction "A_A") (pintype "passive"))
      (node (ref "LED155") (pin "C") (pinfunction "C_C") (pintype "passive"))
      (node (ref "LED156") (pin "A") (pinfunction "A_A") (pintype "passive"))
      (node (ref "LED157") (pin "C") (pinfunction "C_C") (pintype "passive"))
      (node (ref "LED158") (pin "A") (pinfunction "A_A") (pintype "passive"))
      (node (ref "LED159") (pin "C") (pinfunction "C_C") (pintype "passive"))
      (node (ref "LED160") (pin "A") (pinfunction "A_A") (pintype "passive"))
    )
    (net (code "44") (name "Net-(LED153-PadA)") (class "Default")
      (node (ref "LED153") (pin "A") (pinfunction "A_A") (pintype "passive"))
      (node (ref "LED154") (pin "C") (pinfunction "C_C") (pintype "passive"))
      (node (ref "LED33") (pin "A") (pinfunction "A_A") (pintype "passive"))
      (node (ref "LED34") (pin "C") (pinfunction "C_C") (pintype "passive"))
      (node (ref "LED94") (pin "C") (pinfunction "C_C") (pintype "passive"))
      (node (ref "LED95") (pin "A") (pinfunction "A_A") (pintype "passive"))
    )
    (net (code "45") (name "Net-(LED155-PadA)") (class "Default")
      (node (ref "LED155") (pin "A") (pinfunction "A_A") (pintype "passive"))
      (node (ref "LED156") (pin "C") (pinfunction "C_C") (pintype "passive"))
      (node (ref "LED35") (pin "A") (pinfunction "A_A") (pintype "passive"))
      (node (ref "LED36") (pin "C") (pinfunction "C_C") (pintype "passive"))
      (node (ref "LED96") (pin "C") (pinfunction "C_C") (pintype "passive"))
      (node (ref "LED97") (pin "A") (pinfunction "A_A") (pintype "passive"))
    )
    (net (code "46") (name "Net-(LED157-PadA)") (class "Default")
      (node (ref "LED157") (pin "A") (pinfunction "A_A") (pintype "passive"))
      (node (ref "LED158") (pin "C") (pinfunction "C_C") (pintype "passive"))
      (node (ref "LED37") (pin "A") (pinfunction "A_A") (pintype "passive"))
      (node (ref "LED38") (pin "C") (pinfunction "C_C") (pintype "passive"))
      (node (ref "LED98") (pin "C") (pinfunction "C_C") (pintype "passive"))
      (node (ref "LED99") (pin "A") (pinfunction "A_A") (pintype "passive"))
    )
    (net (code "47") (name "Net-(LED161-PadC)") (class "Default")
      (node (ref "LED161") (pin "C") (pinfunction "C_C") (pintype "passive"))
      (node (ref "LED162") (pin "A") (pinfunction "A_A") (pintype "passive"))
      (node (ref "LED163") (pin "C") (pinfunction "C_C") (pintype "passive"))
      (node (ref "LED164") (pin "A") (pinfunction "A_A") (pintype "passive"))
      (node (ref "LED165") (pin "C") (pinfunction "C_C") (pintype "passive"))
      (node (ref "LED166") (pin "A") (pinfunction "A_A") (pintype "passive"))
      (node (ref "LED167") (pin "C") (pinfunction "C_C") (pintype "passive"))
      (node (ref "LED168") (pin "A") (pinfunction "A_A") (pintype "passive"))
      (node (ref "LED169") (pin "C") (pinfunction "C_C") (pintype "passive"))
      (node (ref "LED170") (pin "A") (pinfunction "A_A") (pintype "passive"))
    )
    (net (code "48") (name "Net-(LED171-PadC)") (class "Default")
      (node (ref "LED171") (pin "C") (pinfunction "C_C") (pintype "passive"))
      (node (ref "LED172") (pin "A") (pinfunction "A_A") (pintype "passive"))
      (node (ref "LED173") (pin "C") (pinfunction "C_C") (pintype "passive"))
      (node (ref "LED174") (pin "A") (pinfunction "A_A") (pintype "passive"))
      (node (ref "LED175") (pin "C") (pinfunction "C_C") (pintype "passive"))
      (node (ref "LED176") (pin "A") (pinfunction "A_A") (pintype "passive"))
      (node (ref "LED177") (pin "C") (pinfunction "C_C") (pintype "passive"))
      (node (ref "LED178") (pin "A") (pinfunction "A_A") (pintype "passive"))
      (node (ref "LED179") (pin "C") (pinfunction "C_C") (pintype "passive"))
      (node (ref "LED180") (pin "A") (pinfunction "A_A") (pintype "passive"))
    )
  )
)
